# dimmer.net
KiCad netlist of a schematic drawn in EAGLE
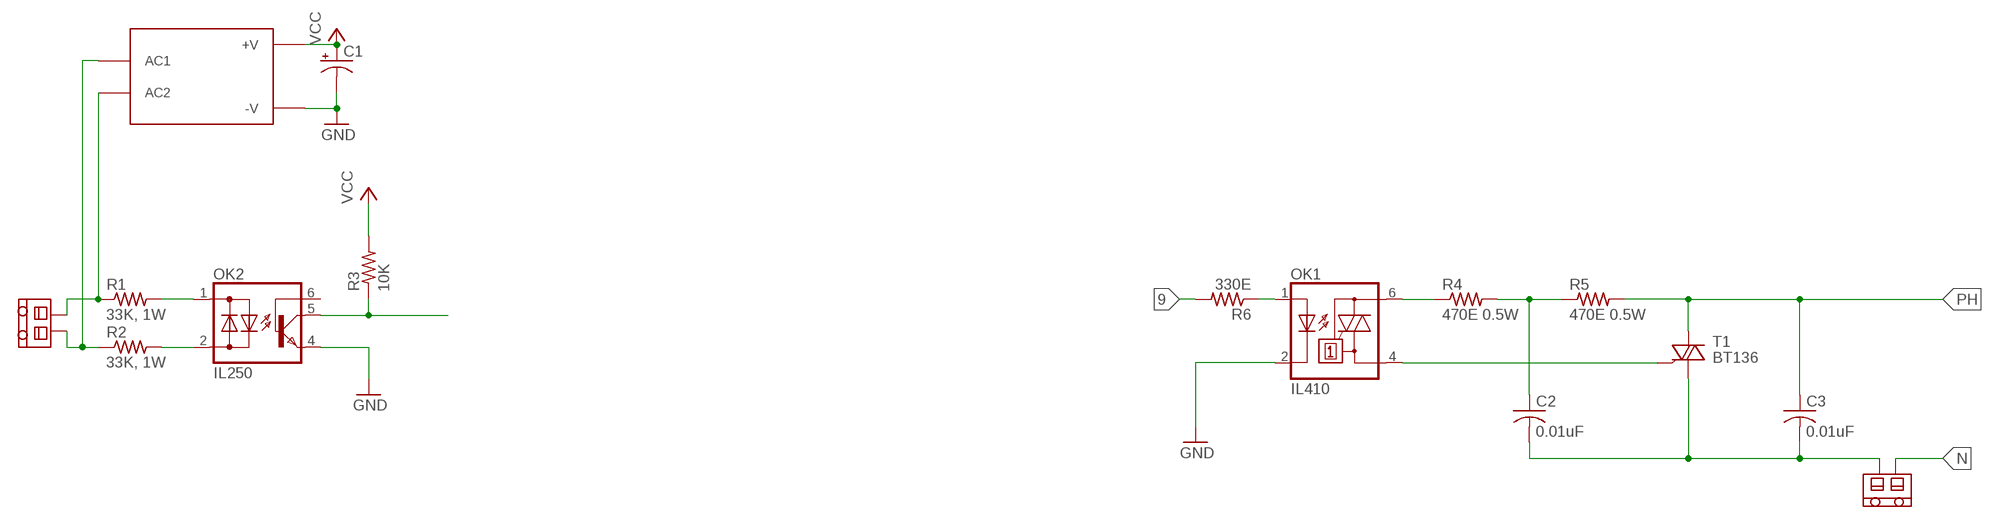
[diagram p0: schematic, sheet 1]

(export (version "E")
  (design (tool "Eeschema 10.0.6"))
  (components
    (comp (ref "C1")
      (value "CPOL-US153CLV-0807")
      (footprint "eagle-import:153CLV-0807")
      (libsource (lib "eagle-import") (part "CPOL-US153CLV-0807"))
    )
    (comp (ref "C2")
      (value "0.01uF")
      (footprint "eagle-import:C075-032X103")
      (libsource (lib "eagle-import") (part "C-US075-032X103"))
    )
    (comp (ref "C3")
      (value "0.01uF")
      (footprint "eagle-import:C075-032X103")
      (libsource (lib "eagle-import") (part "C-US075-032X103"))
    )
    (comp (ref "OK1")
      (value "IL410")
      (footprint "eagle-import:DIL06")
      (fields (field (name "MF") "VISHAY/TELEFUNKEN"))
      (libsource (lib "eagle-import") (part "IL410"))
    )
    (comp (ref "OK2")
      (value "IL250")
      (footprint "eagle-import:DIL06")
      (fields (field (name "MF") "VISHAY/TELEFUNKEN"))
      (libsource (lib "eagle-import") (part "IL250"))
    )
    (comp (ref "R1")
      (value "33K, 1W")
      (footprint "eagle-import:0207_10")
      (libsource (lib "eagle-import") (part "R-US_0207/10"))
    )
    (comp (ref "R2")
      (value "33K, 1W")
      (footprint "eagle-import:0207_10")
      (libsource (lib "eagle-import") (part "R-US_0207/10"))
    )
    (comp (ref "R3")
      (value "10K")
      (footprint "eagle-import:M0805")
      (libsource (lib "eagle-import") (part "R-US_M0805"))
    )
    (comp (ref "R4")
      (value "470E 0.5W")
      (footprint "eagle-import:0207_12")
      (libsource (lib "eagle-import") (part "R-US_0207/12"))
    )
    (comp (ref "R5")
      (value "470E 0.5W")
      (footprint "eagle-import:0207_12")
      (libsource (lib "eagle-import") (part "R-US_0207/12"))
    )
    (comp (ref "R6")
      (value "330E")
      (footprint "eagle-import:M1206")
      (libsource (lib "eagle-import") (part "R-US_M1206"))
    )
    (comp (ref "T1")
      (value "BT136")
      (footprint "eagle-import:TO220AB")
      (libsource (lib "eagle-import") (part "BT136"))
    )
    (comp (ref "U$1")
      (value "DC_ADAPTER")
      (footprint "eagle-import:DC_ADAPTER")
      (libsource (lib "eagle-import") (part "DC_ADAPTER"))
    )
    (comp (ref "U$2")
      (value "TERMINAL_BLOCK")
      (footprint "eagle-import:TERMINAL_BLOCK")
      (libsource (lib "eagle-import") (part "TERMINAL_BLOCK"))
    )
    (comp (ref "U$3")
      (value "TERMINAL_BLOCK")
      (footprint "eagle-import:TERMINAL_BLOCK")
      (libsource (lib "eagle-import") (part "TERMINAL_BLOCK"))
    )
  )
  (nets
    (net (code "1") (name "9") (class "Default")
      (node (ref "R6") (pin "2") (pinfunction "2_2") (pintype "passive"))
    )
    (net (code "2") (name "GND") (class "Default")
      (node (ref "C1") (pin "-") (pinfunction "-_-") (pintype "passive"))
      (node (ref "OK1") (pin "2") (pinfunction "C_2") (pintype "passive"))
      (node (ref "OK2") (pin "4") (pinfunction "E_4") (pintype "passive"))
      (node (ref "U$1") (pin "V-") (pinfunction "-V_V-") (pintype "bidirectional"))
    )
    (net (code "3") (name "N") (class "Default")
      (node (ref "R2") (pin "1") (pinfunction "1_1") (pintype "passive"))
      (node (ref "U$1") (pin "AC1") (pinfunction "AC1_AC1") (pintype "bidirectional"))
      (node (ref "U$2") (pin "1") (pinfunction "P$1_1") (pintype "bidirectional"))
      (node (ref "U$3") (pin "1") (pinfunction "P$1_1") (pintype "bidirectional"))
    )
    (net (code "4") (name "Net-(C2-Pad1)") (class "Default")
      (node (ref "C2") (pin "1") (pinfunction "1_1") (pintype "passive"))
      (node (ref "R4") (pin "2") (pinfunction "2_2") (pintype "passive"))
      (node (ref "R5") (pin "1") (pinfunction "1_1") (pintype "passive"))
    )
    (net (code "5") (name "Net-(OK1-A)") (class "Default")
      (node (ref "OK1") (pin "1") (pinfunction "A_1") (pintype "passive"))
      (node (ref "R6") (pin "1") (pinfunction "1_1") (pintype "passive"))
    )
    (net (code "6") (name "Net-(OK1-A1)") (class "Default")
      (node (ref "OK1") (pin "4") (pinfunction "A1_4") (pintype "passive"))
      (node (ref "T1") (pin "3") (pinfunction "G_3") (pintype "passive"))
    )
    (net (code "7") (name "Net-(OK1-A2)") (class "Default")
      (node (ref "OK1") (pin "6") (pinfunction "A2_6") (pintype "passive"))
      (node (ref "R4") (pin "1") (pinfunction "1_1") (pintype "passive"))
    )
    (net (code "8") (name "Net-(OK2-AC1)") (class "Default")
      (node (ref "OK2") (pin "1") (pinfunction "AC1_1") (pintype "passive"))
      (node (ref "R1") (pin "2") (pinfunction "2_2") (pintype "passive"))
    )
    (net (code "9") (name "Net-(OK2-AC2)") (class "Default")
      (node (ref "OK2") (pin "2") (pinfunction "AC2_2") (pintype "passive"))
      (node (ref "R2") (pin "2") (pinfunction "2_2") (pintype "passive"))
    )
    (net (code "10") (name "Net-(OK2-C)") (class "Default")
      (node (ref "OK2") (pin "5") (pinfunction "C_5") (pintype "passive"))
      (node (ref "R3") (pin "1") (pinfunction "1_1") (pintype "passive"))
    )
    (net (code "11") (name "Net-(T1-A1)") (class "Default")
      (node (ref "C2") (pin "2") (pinfunction "2_2") (pintype "passive"))
      (node (ref "C3") (pin "2") (pinfunction "2_2") (pintype "passive"))
      (node (ref "T1") (pin "1") (pinfunction "A1_1") (pintype "passive"))
      (node (ref "U$3") (pin "2") (pinfunction "P$2_2") (pintype "bidirectional"))
    )
    (net (code "12") (name "PH") (class "Default")
      (node (ref "C3") (pin "1") (pinfunction "1_1") (pintype "passive"))
      (node (ref "R1") (pin "1") (pinfunction "1_1") (pintype "passive"))
      (node (ref "R5") (pin "2") (pinfunction "2_2") (pintype "passive"))
      (node (ref "T1") (pin "2") (pinfunction "A2_2") (pintype "passive"))
      (node (ref "U$1") (pin "AC2") (pinfunction "AC2_AC2") (pintype "bidirectional"))
      (node (ref "U$2") (pin "2") (pinfunction "P$2_2") (pintype "bidirectional"))
    )
    (net (code "13") (name "VCC") (class "Default")
      (node (ref "C1") (pin "+") (pinfunction "+_+") (pintype "passive"))
      (node (ref "R3") (pin "2") (pinfunction "2_2") (pintype "passive"))
      (node (ref "U$1") (pin "V+") (pinfunction "+V_V+") (pintype "bidirectional"))
    )
    (net (code "14") (name "unconnected-(OK2-B-Pad6)") (class "Default")
      (node (ref "OK2") (pin "6") (pinfunction "B_6") (pintype "passive"))
    )
  )
)
